# schematic.net
KiCad netlist of a schematic drawn in Altium Designer
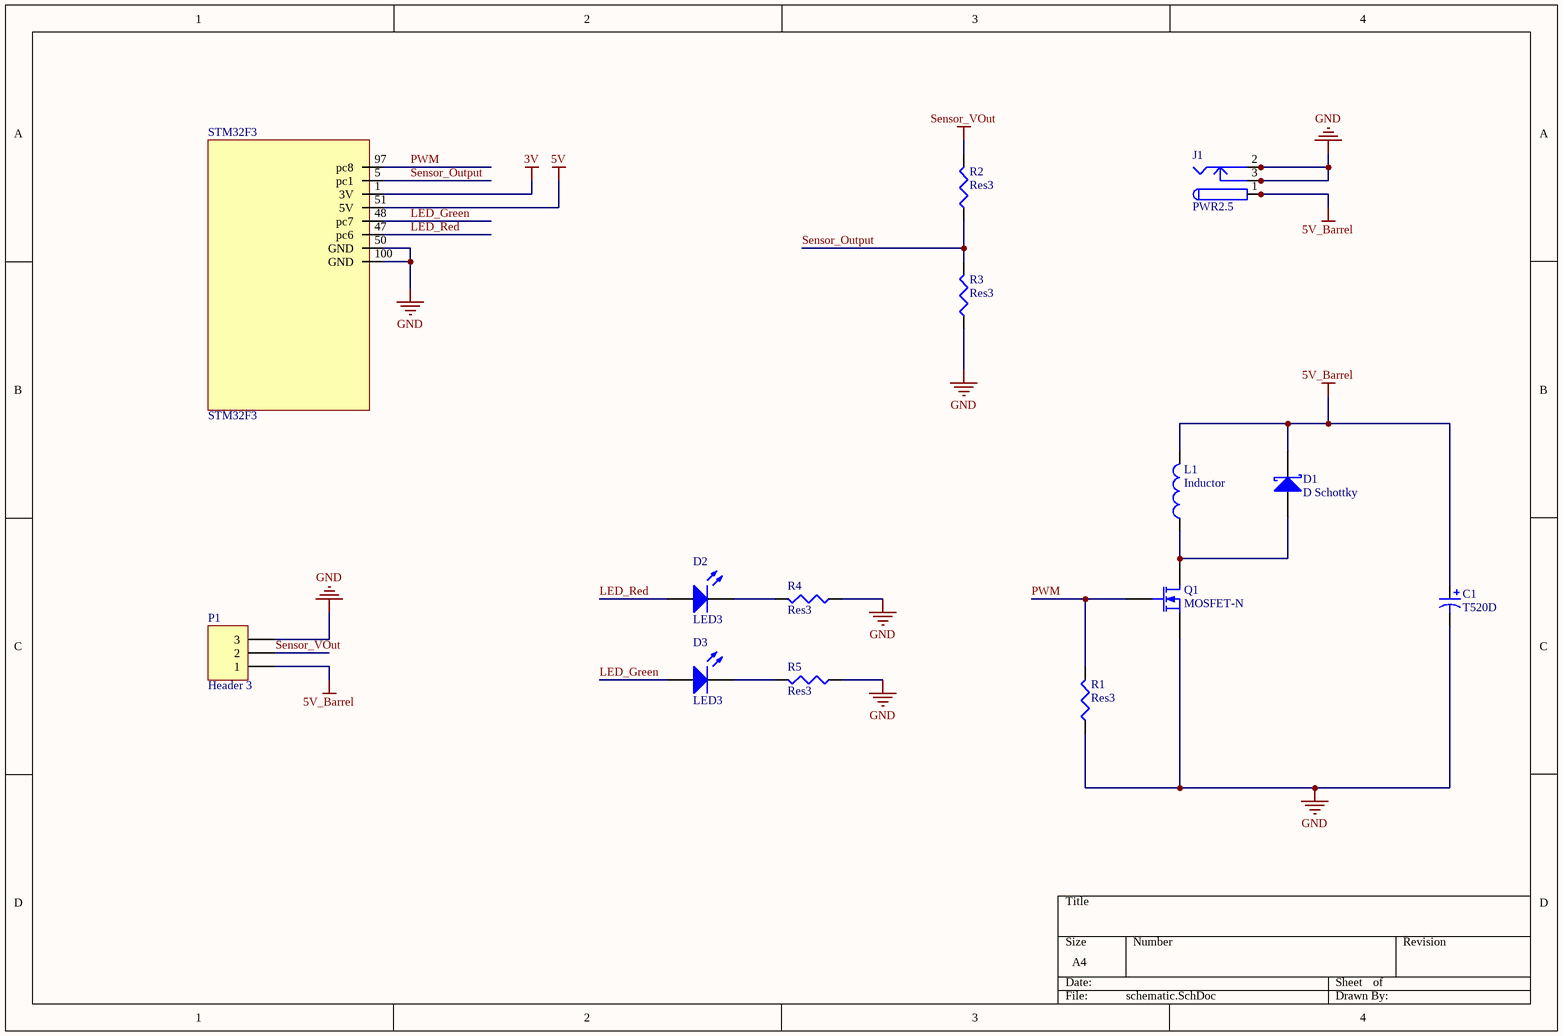
[diagram p0: schematic.SchDoc]

(export (version "E")
  (design (tool "Eeschema 10.0.6"))
  (components
    (comp (ref "C1")
      (value "T520D")
      (footprint "D")
      (description "Polymer Tantalum Chip Capacitor, T520 Series - KO-CAP Polymer")
      (fields (field (name "PUBLISHER") "Altium Limited"))
      (libsource (lib "KEMET Chip Capacitor") (part "T520D"))
    )
    (comp (ref "D1")
      (value "D Schottky")
      (footprint "SMB")
      (description "Schottky Diode")
      (fields (field (name "PUBLISHER") "Altium Limited"))
      (libsource (lib "Miscellaneous Devices") (part "D Schottky"))
    )
    (comp (ref "D2")
      (value "LED3")
      (footprint "3.5X2.8X1.9")
      (description "Typical BLUE SiC LED")
      (fields (field (name "PUBLISHER") "Altium Limited"))
      (libsource (lib "Miscellaneous Devices") (part "LED3"))
    )
    (comp (ref "D3")
      (value "LED3")
      (footprint "3.5X2.8X1.9")
      (description "Typical BLUE SiC LED")
      (fields (field (name "PUBLISHER") "Altium Limited"))
      (libsource (lib "Miscellaneous Devices") (part "LED3"))
    )
    (comp (ref "J1")
      (value "PWR2.5")
      (footprint "KLD-0202")
      (description "Low Voltage Power Supply Connector")
      (fields (field (name "PUBLISHER") "Altium Limited"))
      (libsource (lib "Miscellaneous Connectors") (part "PWR2.5"))
    )
    (comp (ref "L1")
      (value "Inductor")
      (footprint "0402-A")
      (fields (field (name "PUBLISHER") "Altium Limited"))
      (libsource (lib "Miscellaneous Devices") (part "Inductor"))
    )
    (comp (ref "P1")
      (value "Header 3")
      (footprint "HDR1X3")
      (description "Header, 3-Pin")
      (fields (field (name "PUBLISHER") "Altium Limited"))
      (libsource (lib "Miscellaneous Connectors") (part "Header 3"))
    )
    (comp (ref "Q1")
      (value "MOSFET-N")
      (footprint "E3")
      (description "N-Channel MOSFET")
      (fields (field (name "PUBLISHER") "Altium Limited"))
      (libsource (lib "Miscellaneous Devices") (part "MOSFET-N"))
    )
    (comp (ref "R1")
      (value "Res3")
      (footprint "J1-0603")
      (description "Resistor")
      (fields (field (name "PUBLISHER") "Altium Limited"))
      (libsource (lib "Miscellaneous Devices") (part "Res3"))
    )
    (comp (ref "R2")
      (value "Res3")
      (footprint "J1-0603")
      (description "Resistor")
      (fields (field (name "PUBLISHER") "Altium Limited"))
      (libsource (lib "Miscellaneous Devices") (part "Res3"))
    )
    (comp (ref "R3")
      (value "Res3")
      (footprint "J1-0603")
      (description "Resistor")
      (fields (field (name "PUBLISHER") "Altium Limited"))
      (libsource (lib "Miscellaneous Devices") (part "Res3"))
    )
    (comp (ref "R4")
      (value "Res3")
      (footprint "J1-0603")
      (description "Resistor")
      (fields (field (name "PUBLISHER") "Altium Limited"))
      (libsource (lib "Miscellaneous Devices") (part "Res3"))
    )
    (comp (ref "R5")
      (value "Res3")
      (footprint "J1-0603")
      (description "Resistor")
      (fields (field (name "PUBLISHER") "Altium Limited"))
      (libsource (lib "Miscellaneous Devices") (part "Res3"))
    )
    (comp (ref "STM32F3")
      (value "STM32F3")
      (footprint "STM32_MagLev")
      (description "STM32F3 base")
      (libsource (lib "Schematic Components") (part "STM32F3"))
    )
  )
  (nets
    (net (code "1") (name "/LED_Green") (class "Default")
      (node (ref "D3") (pin "1") (pinfunction "A_1") (pintype "passive"))
      (node (ref "STM32F3") (pin "48") (pinfunction "pc7_48") (pintype "passive"))
    )
    (net (code "2") (name "/LED_Red") (class "Default")
      (node (ref "D2") (pin "1") (pinfunction "A_1") (pintype "passive"))
      (node (ref "STM32F3") (pin "47") (pinfunction "pc6_47") (pintype "passive"))
    )
    (net (code "3") (name "/PWM") (class "Default")
      (node (ref "Q1") (pin "2") (pinfunction "G_2") (pintype "passive"))
      (node (ref "R1") (pin "2") (pinfunction "2_2") (pintype "passive"))
      (node (ref "STM32F3") (pin "97") (pinfunction "pc8_97") (pintype "passive"))
    )
    (net (code "4") (name "/Sensor_Output") (class "Default")
      (node (ref "R2") (pin "1") (pinfunction "1_1") (pintype "passive"))
      (node (ref "R3") (pin "2") (pinfunction "2_2") (pintype "passive"))
      (node (ref "STM32F3") (pin "5") (pinfunction "pc1_5") (pintype "passive"))
    )
    (net (code "5") (name "3V") (class "Default")
      (node (ref "STM32F3") (pin "1") (pinfunction "3V_1") (pintype "passive"))
    )
    (net (code "6") (name "5V") (class "Default")
      (node (ref "STM32F3") (pin "51") (pinfunction "5V_51") (pintype "passive"))
    )
    (net (code "7") (name "5V_Barrel") (class "Default")
      (node (ref "C1") (pin "1") (pinfunction "1_1") (pintype "passive"))
      (node (ref "D1") (pin "2") (pinfunction "K_2") (pintype "passive"))
      (node (ref "J1") (pin "1") (pinfunction "1_1") (pintype "power_in"))
      (node (ref "J1") (pin "1A") (pinfunction "1A_1A") (pintype "power_in"))
      (node (ref "J1") (pin "1B") (pinfunction "1B_1B") (pintype "power_in"))
      (node (ref "L1") (pin "2") (pinfunction "2_2") (pintype "passive"))
      (node (ref "P1") (pin "1") (pinfunction "1_1") (pintype "passive"))
    )
    (net (code "8") (name "GND") (class "Default")
      (node (ref "C1") (pin "2") (pinfunction "2_2") (pintype "passive"))
      (node (ref "J1") (pin "2") (pinfunction "2_2") (pintype "power_in"))
      (node (ref "J1") (pin "2A") (pinfunction "2A_2A") (pintype "power_in"))
      (node (ref "J1") (pin "2B") (pinfunction "2B_2B") (pintype "power_in"))
      (node (ref "J1") (pin "3") (pinfunction "3_3") (pintype "power_in"))
      (node (ref "J1") (pin "3A") (pinfunction "3A_3A") (pintype "power_in"))
      (node (ref "J1") (pin "3B") (pinfunction "3B_3B") (pintype "power_in"))
      (node (ref "P1") (pin "3") (pinfunction "3_3") (pintype "passive"))
      (node (ref "Q1") (pin "3") (pinfunction "S_3") (pintype "passive"))
      (node (ref "R1") (pin "1") (pinfunction "1_1") (pintype "passive"))
      (node (ref "R3") (pin "1") (pinfunction "1_1") (pintype "passive"))
      (node (ref "R4") (pin "1") (pinfunction "1_1") (pintype "passive"))
      (node (ref "R5") (pin "1") (pinfunction "1_1") (pintype "passive"))
      (node (ref "STM32F3") (pin "100") (pinfunction "GND_100") (pintype "passive"))
      (node (ref "STM32F3") (pin "50") (pinfunction "GND_50") (pintype "passive"))
    )
    (net (code "9") (name "Net-(D1-A)") (class "Default")
      (node (ref "D1") (pin "1") (pinfunction "A_1") (pintype "passive"))
      (node (ref "L1") (pin "1") (pinfunction "1_1") (pintype "passive"))
      (node (ref "Q1") (pin "1") (pinfunction "D_1") (pintype "passive"))
    )
    (net (code "10") (name "Net-(D2-K)") (class "Default")
      (node (ref "D2") (pin "2") (pinfunction "K_2") (pintype "passive"))
      (node (ref "R4") (pin "2") (pinfunction "2_2") (pintype "passive"))
    )
    (net (code "11") (name "Net-(D3-K)") (class "Default")
      (node (ref "D3") (pin "2") (pinfunction "K_2") (pintype "passive"))
      (node (ref "R5") (pin "2") (pinfunction "2_2") (pintype "passive"))
    )
    (net (code "12") (name "Sensor_VOut") (class "Default")
      (node (ref "P1") (pin "2") (pinfunction "2_2") (pintype "passive"))
      (node (ref "R2") (pin "2") (pinfunction "2_2") (pintype "passive"))
    )
  )
)
